# IOport.net
KiCad netlist of a schematic drawn in Altium Designer
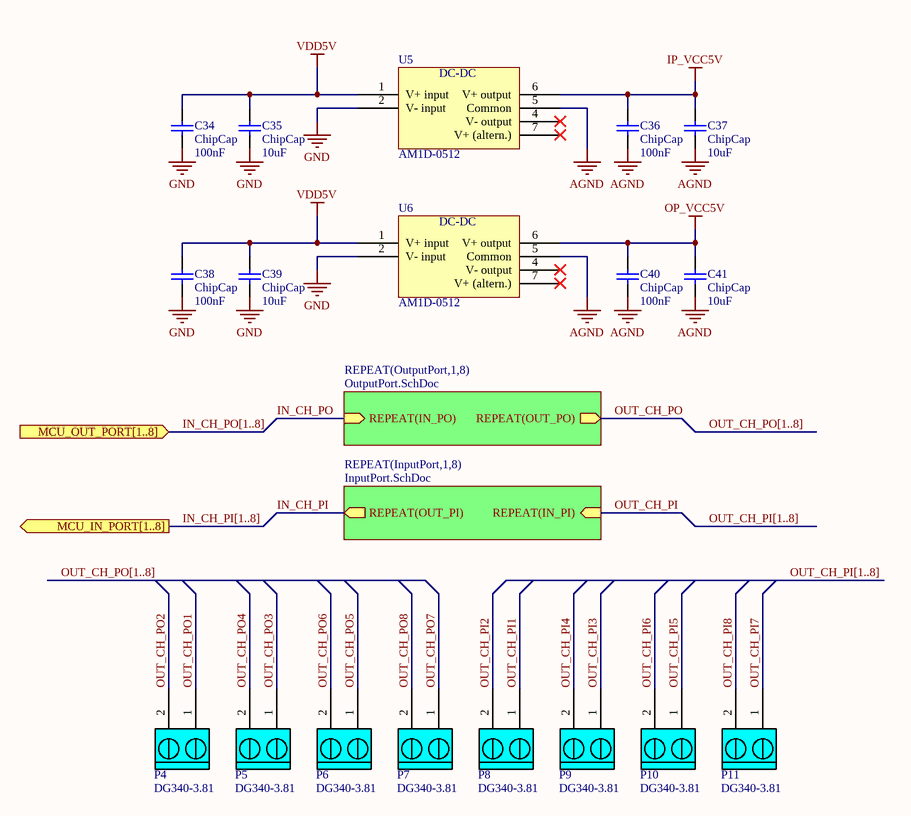
[diagram p0: IOport.SchDoc]

(export (version "E")
  (design (tool "Eeschema 10.0.6"))
  (components
    (comp (ref "C34")
      (value "ChipCap")
      (footprint "CAP0805")
      (description "Capacitor")
      (fields (field (name "ALTIUM_VALUE") "100nF") (field (name "PUBLISHER") "Altium Limited"))
      (libsource (lib "Common Devices") (part "ChipCap"))
    )
    (comp (ref "C35")
      (value "ChipCap")
      (footprint "CAP0805")
      (description "Capacitor")
      (fields (field (name "ALTIUM_VALUE") "10uF") (field (name "PUBLISHER") "Altium Limited"))
      (libsource (lib "Common Devices") (part "ChipCap"))
    )
    (comp (ref "C36")
      (value "ChipCap")
      (footprint "CAP0805")
      (description "Capacitor")
      (fields (field (name "ALTIUM_VALUE") "100nF") (field (name "PUBLISHER") "Altium Limited"))
      (libsource (lib "Common Devices") (part "ChipCap"))
    )
    (comp (ref "C37")
      (value "ChipCap")
      (footprint "CAP0805")
      (description "Capacitor")
      (fields (field (name "ALTIUM_VALUE") "10uF") (field (name "PUBLISHER") "Altium Limited"))
      (libsource (lib "Common Devices") (part "ChipCap"))
    )
    (comp (ref "C38")
      (value "ChipCap")
      (footprint "CAP0805")
      (description "Capacitor")
      (fields (field (name "ALTIUM_VALUE") "100nF") (field (name "PUBLISHER") "Altium Limited"))
      (libsource (lib "Common Devices") (part "ChipCap"))
    )
    (comp (ref "C39")
      (value "ChipCap")
      (footprint "CAP0805")
      (description "Capacitor")
      (fields (field (name "ALTIUM_VALUE") "10uF") (field (name "PUBLISHER") "Altium Limited"))
      (libsource (lib "Common Devices") (part "ChipCap"))
    )
    (comp (ref "C40")
      (value "ChipCap")
      (footprint "CAP0805")
      (description "Capacitor")
      (fields (field (name "ALTIUM_VALUE") "100nF") (field (name "PUBLISHER") "Altium Limited"))
      (libsource (lib "Common Devices") (part "ChipCap"))
    )
    (comp (ref "C41")
      (value "ChipCap")
      (footprint "CAP0805")
      (description "Capacitor")
      (fields (field (name "ALTIUM_VALUE") "10uF") (field (name "PUBLISHER") "Altium Limited"))
      (libsource (lib "Common Devices") (part "ChipCap"))
    )
    (comp (ref "P4")
      (value "DG340-3.81")
      (footprint "DG340-3.81-02P-00A(H)")
      (description "Terminal block")
      (libsource (lib "Connectors") (part "DG340-3.81-02P"))
    )
    (comp (ref "P5")
      (value "DG340-3.81")
      (footprint "DG340-3.81-02P-00A(H)")
      (description "Terminal block")
      (libsource (lib "Connectors") (part "DG340-3.81-02P"))
    )
    (comp (ref "P6")
      (value "DG340-3.81")
      (footprint "DG340-3.81-02P-00A(H)")
      (description "Terminal block")
      (libsource (lib "Connectors") (part "DG340-3.81-02P"))
    )
    (comp (ref "P7")
      (value "DG340-3.81")
      (footprint "DG340-3.81-02P-00A(H)")
      (description "Terminal block")
      (libsource (lib "Connectors") (part "DG340-3.81-02P"))
    )
    (comp (ref "P8")
      (value "DG340-3.81")
      (footprint "DG340-3.81-02P-00A(H)")
      (description "Terminal block")
      (libsource (lib "Connectors") (part "DG340-3.81-02P"))
    )
    (comp (ref "P9")
      (value "DG340-3.81")
      (footprint "DG340-3.81-02P-00A(H)")
      (description "Terminal block")
      (libsource (lib "Connectors") (part "DG340-3.81-02P"))
    )
    (comp (ref "P10")
      (value "DG340-3.81")
      (footprint "DG340-3.81-02P-00A(H)")
      (description "Terminal block")
      (libsource (lib "Connectors") (part "DG340-3.81-02P"))
    )
    (comp (ref "P11")
      (value "DG340-3.81")
      (footprint "DG340-3.81-02P-00A(H)")
      (description "Terminal block")
      (libsource (lib "Connectors") (part "DG340-3.81-02P"))
    )
    (comp (ref "U5")
      (value "AM1D-0512")
      (footprint "SIP14")
      (description "DC-DC 5-12V convertor")
      (libsource (lib "Aimtec DC-DC converter") (part "AM1D-0512"))
    )
    (comp (ref "U6")
      (value "AM1D-0512")
      (footprint "SIP14")
      (description "DC-DC 5-12V convertor")
      (libsource (lib "Aimtec DC-DC converter") (part "AM1D-0512"))
    )
  )
  (nets
    (net (code "22") (name "/OUT_CH_PI1") (class "Default")
      (node (ref "P8") (pin "1") (pinfunction "1_1") (pintype "passive"))
    )
    (net (code "23") (name "/OUT_CH_PI2") (class "Default")
      (node (ref "P8") (pin "2") (pinfunction "2_2") (pintype "passive"))
    )
    (net (code "24") (name "/OUT_CH_PI3") (class "Default")
      (node (ref "P9") (pin "1") (pinfunction "1_1") (pintype "passive"))
    )
    (net (code "25") (name "/OUT_CH_PI4") (class "Default")
      (node (ref "P9") (pin "2") (pinfunction "2_2") (pintype "passive"))
    )
    (net (code "26") (name "/OUT_CH_PI5") (class "Default")
      (node (ref "P10") (pin "1") (pinfunction "1_1") (pintype "passive"))
    )
    (net (code "27") (name "/OUT_CH_PI6") (class "Default")
      (node (ref "P10") (pin "2") (pinfunction "2_2") (pintype "passive"))
    )
    (net (code "28") (name "/OUT_CH_PI7") (class "Default")
      (node (ref "P11") (pin "1") (pinfunction "1_1") (pintype "passive"))
    )
    (net (code "29") (name "/OUT_CH_PI8") (class "Default")
      (node (ref "P11") (pin "2") (pinfunction "2_2") (pintype "passive"))
    )
    (net (code "32") (name "/OUT_CH_PO1") (class "Default")
      (node (ref "P4") (pin "1") (pinfunction "1_1") (pintype "passive"))
    )
    (net (code "33") (name "/OUT_CH_PO2") (class "Default")
      (node (ref "P4") (pin "2") (pinfunction "2_2") (pintype "passive"))
    )
    (net (code "34") (name "/OUT_CH_PO3") (class "Default")
      (node (ref "P5") (pin "1") (pinfunction "1_1") (pintype "passive"))
    )
    (net (code "35") (name "/OUT_CH_PO4") (class "Default")
      (node (ref "P5") (pin "2") (pinfunction "2_2") (pintype "passive"))
    )
    (net (code "36") (name "/OUT_CH_PO5") (class "Default")
      (node (ref "P6") (pin "1") (pinfunction "1_1") (pintype "passive"))
    )
    (net (code "37") (name "/OUT_CH_PO6") (class "Default")
      (node (ref "P6") (pin "2") (pinfunction "2_2") (pintype "passive"))
    )
    (net (code "38") (name "/OUT_CH_PO7") (class "Default")
      (node (ref "P7") (pin "1") (pinfunction "1_1") (pintype "passive"))
    )
    (net (code "39") (name "/OUT_CH_PO8") (class "Default")
      (node (ref "P7") (pin "2") (pinfunction "2_2") (pintype "passive"))
    )
    (net (code "41") (name "AGND") (class "Default")
      (node (ref "C36") (pin "1") (pinfunction "1_1") (pintype "passive"))
      (node (ref "C37") (pin "1") (pinfunction "1_1") (pintype "passive"))
      (node (ref "C40") (pin "1") (pinfunction "1_1") (pintype "passive"))
      (node (ref "C41") (pin "1") (pinfunction "1_1") (pintype "passive"))
      (node (ref "U5") (pin "5") (pinfunction "Common_5") (pintype "passive"))
      (node (ref "U6") (pin "5") (pinfunction "Common_5") (pintype "passive"))
    )
    (net (code "42") (name "GND") (class "Default")
      (node (ref "C34") (pin "1") (pinfunction "1_1") (pintype "passive"))
      (node (ref "C35") (pin "1") (pinfunction "1_1") (pintype "passive"))
      (node (ref "C38") (pin "1") (pinfunction "1_1") (pintype "passive"))
      (node (ref "C39") (pin "1") (pinfunction "1_1") (pintype "passive"))
      (node (ref "U5") (pin "2") (pinfunction "V-_input_2") (pintype "passive"))
      (node (ref "U6") (pin "2") (pinfunction "V-_input_2") (pintype "passive"))
    )
    (net (code "43") (name "IP_VCC5V") (class "Default")
      (node (ref "C36") (pin "2") (pinfunction "2_2") (pintype "passive"))
      (node (ref "C37") (pin "2") (pinfunction "2_2") (pintype "passive"))
      (node (ref "U5") (pin "6") (pinfunction "V+_output_6") (pintype "passive"))
    )
    (net (code "44") (name "OP_VCC5V") (class "Default")
      (node (ref "C40") (pin "2") (pinfunction "2_2") (pintype "passive"))
      (node (ref "C41") (pin "2") (pinfunction "2_2") (pintype "passive"))
      (node (ref "U6") (pin "6") (pinfunction "V+_output_6") (pintype "passive"))
    )
    (net (code "45") (name "VDD5V") (class "Default")
      (node (ref "C34") (pin "2") (pinfunction "2_2") (pintype "passive"))
      (node (ref "C35") (pin "2") (pinfunction "2_2") (pintype "passive"))
      (node (ref "C38") (pin "2") (pinfunction "2_2") (pintype "passive"))
      (node (ref "C39") (pin "2") (pinfunction "2_2") (pintype "passive"))
      (node (ref "U5") (pin "1") (pinfunction "V+_input_1") (pintype "passive"))
      (node (ref "U6") (pin "1") (pinfunction "V+_input_1") (pintype "passive"))
    )
    (net (code "46") (name "unconnected-(U5-V+_(altern.)-Pad7)") (class "Default")
      (node (ref "U5") (pin "7") (pinfunction "V+_(altern.)_7") (pintype "passive+no_connect"))
    )
    (net (code "47") (name "unconnected-(U5-V-_output-Pad4)") (class "Default")
      (node (ref "U5") (pin "4") (pinfunction "V-_output_4") (pintype "passive+no_connect"))
    )
    (net (code "48") (name "unconnected-(U6-V+_(altern.)-Pad7)") (class "Default")
      (node (ref "U6") (pin "7") (pinfunction "V+_(altern.)_7") (pintype "passive+no_connect"))
    )
    (net (code "49") (name "unconnected-(U6-V-_output-Pad4)") (class "Default")
      (node (ref "U6") (pin "4") (pinfunction "V-_output_4") (pintype "passive+no_connect"))
    )
  )
)
